# ProPrj_Business-Card.net
KiCad netlist of a schematic drawn in EasyEDA Pro
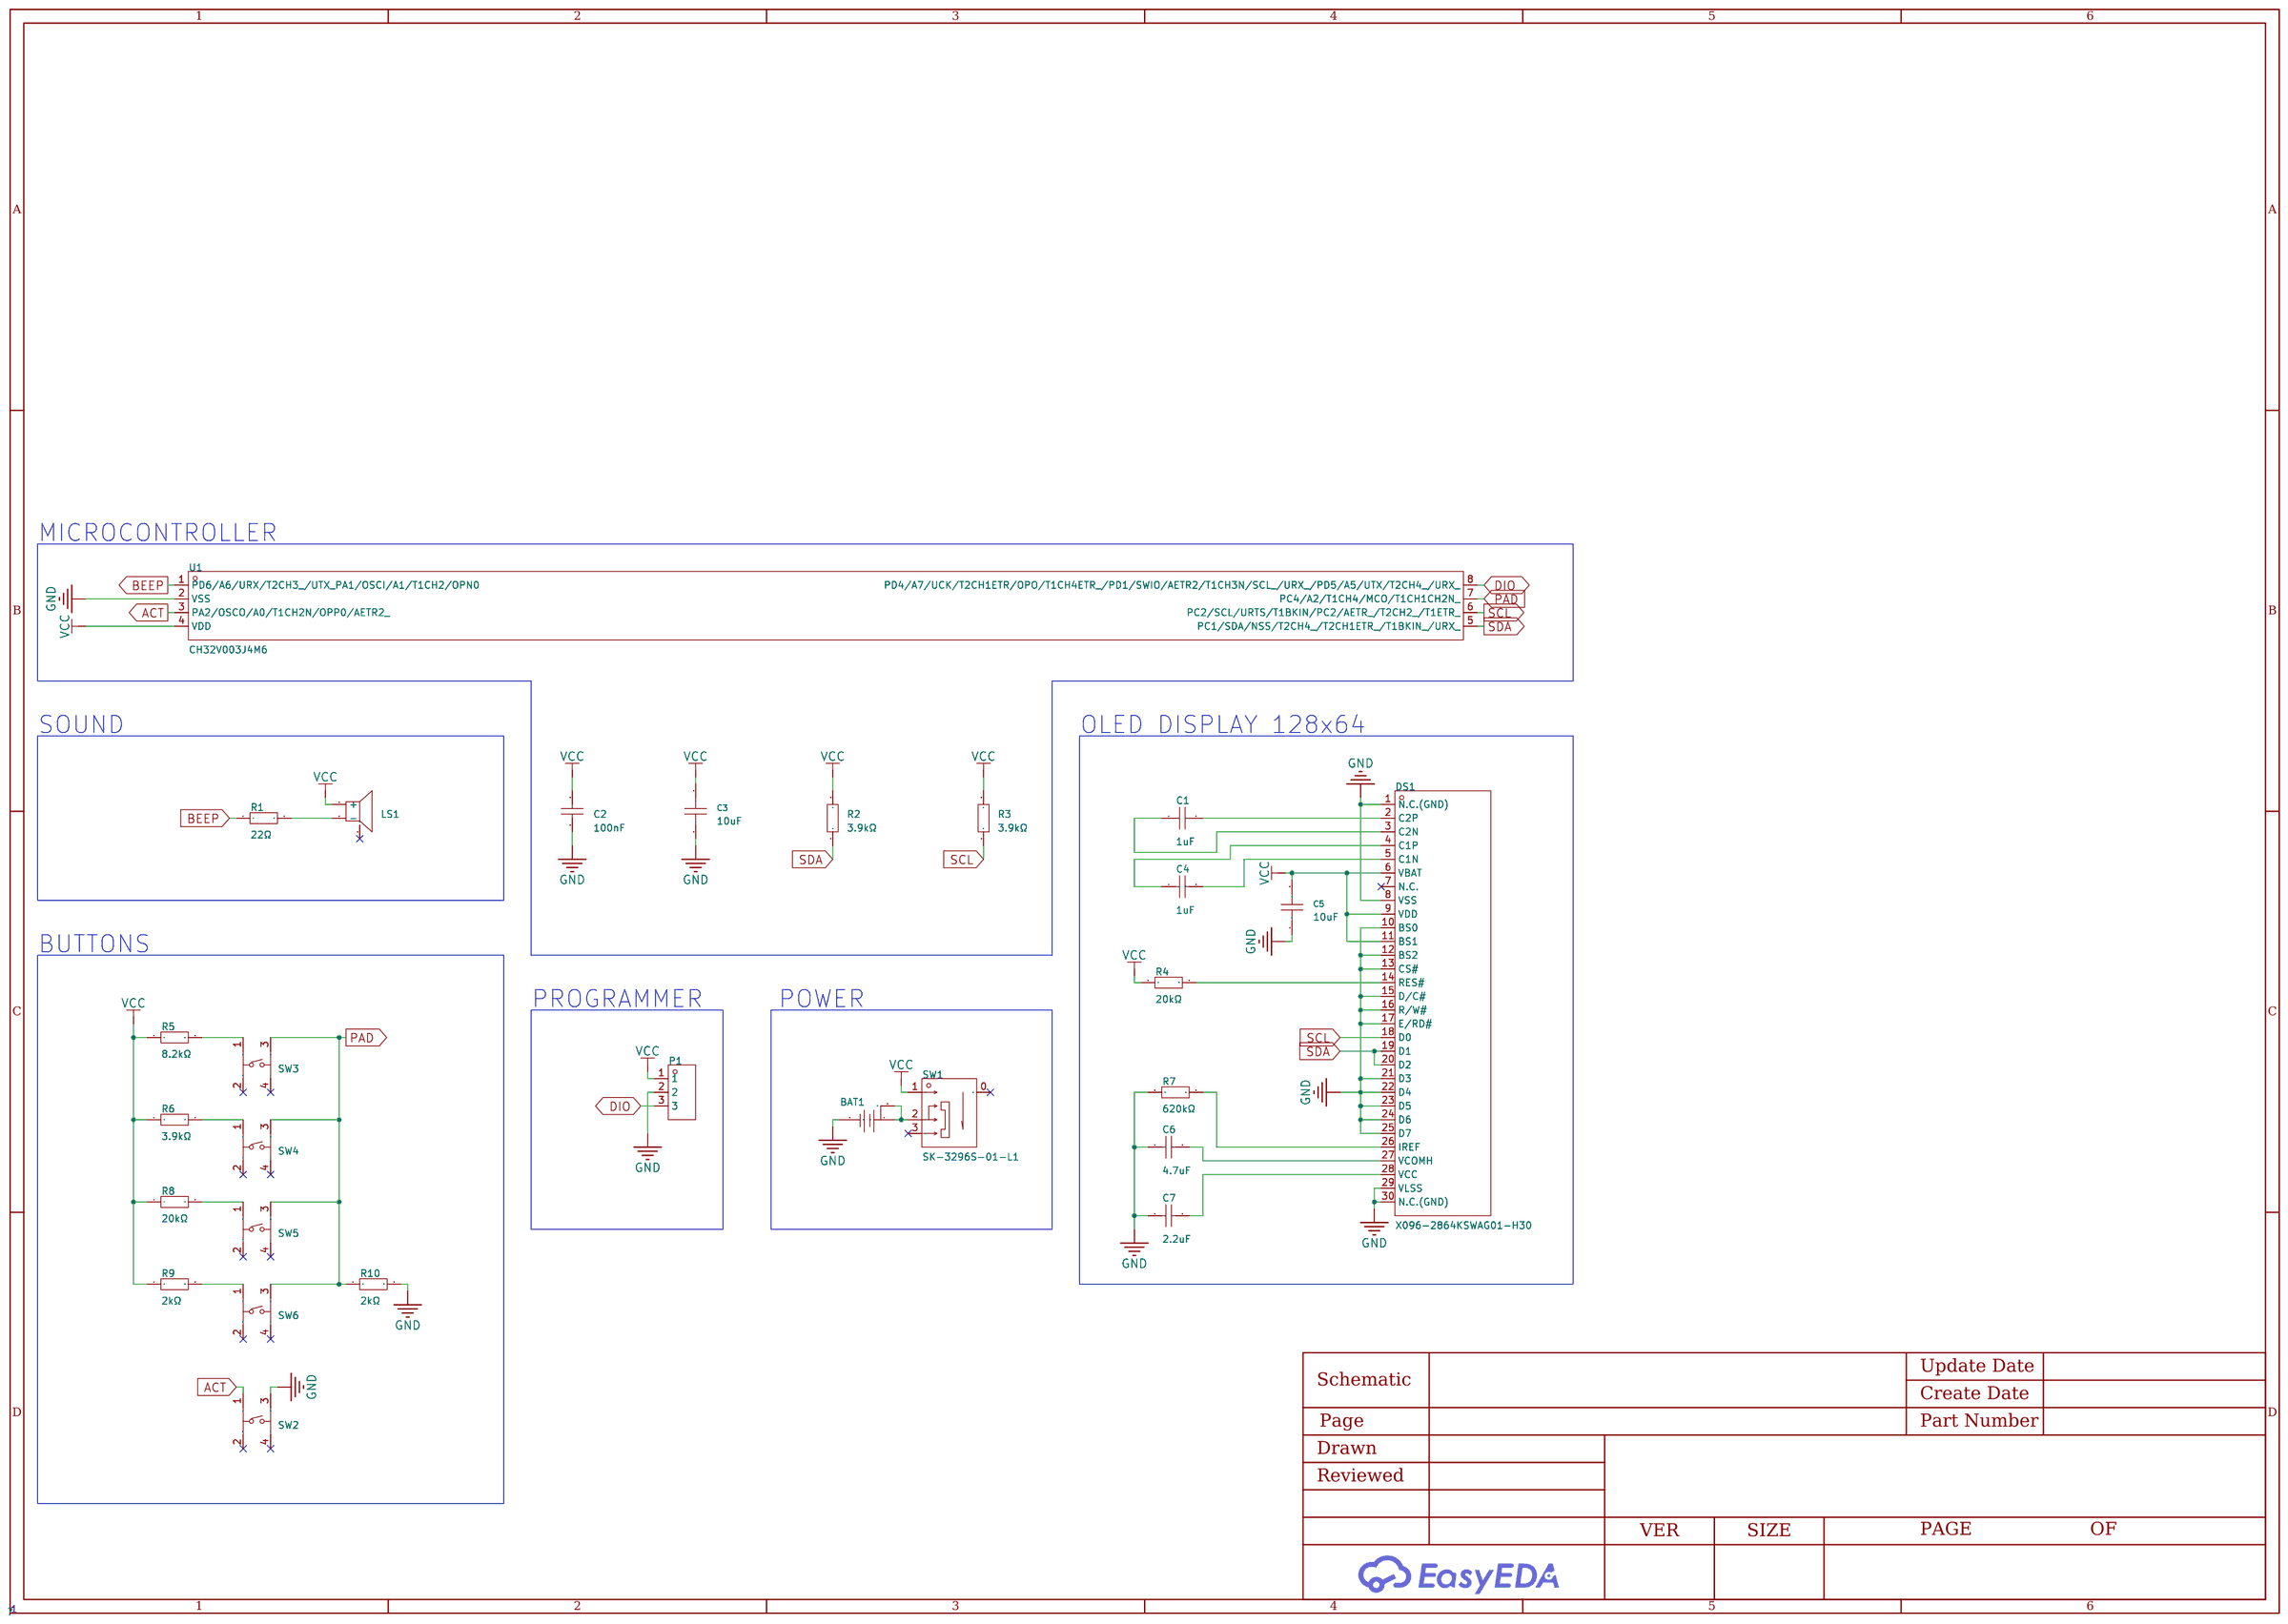
[diagram p0: schematic sheet]

(export (version "E")
  (design (tool "Eeschema 10.0.6"))
  (components
    (comp (ref "BAT1")
      (value "3034TR")
      (footprint "easyedapro:BAT-SMD_3034TR")
      (fields (field (name "Manufacturer") "Keystone"))
      (libsource (lib "easyedapro") (part "3034TR"))
    )
    (comp (ref "C1")
      (value "1uF")
      (footprint "easyedapro:C0805")
      (fields
        (field (name "Manufacturer Part") "GRM21BR71E105KA99L")
        (field (name "Manufacturer") "muRata(村田)")
      )
      (libsource (lib "easyedapro") (part "GRM21BR71E105KA99L"))
    )
    (comp (ref "C2")
      (value "100nF")
      (footprint "easyedapro:C0805")
      (fields
        (field (name "Manufacturer Part") "CC0805KRX7R9BB104")
        (field (name "Manufacturer") "YAGEO(国巨)")
      )
      (libsource (lib "easyedapro") (part "CC0805KRX7R9BB104"))
    )
    (comp (ref "C3")
      (value "10uF")
      (footprint "easyedapro:C0805")
      (fields
        (field (name "Manufacturer Part") "GRM21BR61C106KE15L")
        (field (name "Manufacturer") "muRata(村田)")
      )
      (libsource (lib "easyedapro") (part "GRM21BR61C106KE15L"))
    )
    (comp (ref "C4")
      (value "1uF")
      (footprint "easyedapro:C0805")
      (fields
        (field (name "Manufacturer Part") "GRM21BR71E105KA99L")
        (field (name "Manufacturer") "muRata(村田)")
      )
      (libsource (lib "easyedapro") (part "GRM21BR71E105KA99L"))
    )
    (comp (ref "C5")
      (value "10uF")
      (footprint "easyedapro:C0805")
      (fields
        (field (name "Manufacturer Part") "GRM21BR61C106KE15L")
        (field (name "Manufacturer") "muRata(村田)")
      )
      (libsource (lib "easyedapro") (part "GRM21BR61C106KE15L"))
    )
    (comp (ref "C6")
      (value "4.7uF")
      (footprint "easyedapro:C0805")
      (fields
        (field (name "Manufacturer Part") "GRM21BR61E475KA12L")
        (field (name "Manufacturer") "muRata(村田)")
      )
      (libsource (lib "easyedapro") (part "GRM21BR61E475KA12L"))
    )
    (comp (ref "C7")
      (value "2.2uF")
      (footprint "easyedapro:C0805")
      (fields
        (field (name "Manufacturer Part") "GRM21BR71E225KE11L")
        (field (name "Manufacturer") "muRata(村田)")
      )
      (libsource (lib "easyedapro") (part "GRM21BR71E225KE11L"))
    )
    (comp (ref "DS1")
      (value "X096-2864KSWAG01-H30")
      (footprint "easyedapro:LCD-SMD_X096-2864KSWAG01-H30")
      (description "Main Control Chip:SSD1315 Size:0.96 Pixel Resolution:128x64")
      (fields (field (name "Manufacturer") "Newvision(新智景)"))
      (libsource (lib "easyedapro") (part "X096-2864KSWAG01-H30"))
    )
    (comp (ref "LS1")
      (value "4kHz")
      (footprint "easyedapro:BUZ-SMD_3P-L5.2-W5.2-P3.50-BR")
      (fields (field (name "Manufacturer Part") "MLT-5030") (field (name "Manufacturer") "华能"))
      (libsource (lib "easyedapro") (part "MLT-5030"))
    )
    (comp (ref "P1")
      (value "X6511FRS-03-C85D30")
      (footprint "easyedapro:HDR-SMD_3P-P2.54-H-F-L11.5")
      (fields (field (name "Manufacturer") "XKB Connectivity(中国星坤)"))
      (libsource (lib "easyedapro") (part "X6511FRS-03-C85D30"))
    )
    (comp (ref "R1")
      (value "22Ω")
      (footprint "easyedapro:R0805")
      (fields (field (name "Manufacturer Part") "RC0805FR-0722RL") (field (name "Manufacturer") "YAGEO(国巨)"))
      (libsource (lib "easyedapro") (part "RC0805FR-0722RL"))
    )
    (comp (ref "R2")
      (value "3.9kΩ")
      (footprint "easyedapro:R0805")
      (fields (field (name "Manufacturer Part") "RC0805FR-073K9L") (field (name "Manufacturer") "YAGEO(国巨)"))
      (libsource (lib "easyedapro") (part "RC0805FR-073K9L"))
    )
    (comp (ref "R3")
      (value "3.9kΩ")
      (footprint "easyedapro:R0805")
      (fields (field (name "Manufacturer Part") "RC0805FR-073K9L") (field (name "Manufacturer") "YAGEO(国巨)"))
      (libsource (lib "easyedapro") (part "RC0805FR-073K9L"))
    )
    (comp (ref "R4")
      (value "20kΩ")
      (footprint "easyedapro:R0805")
      (fields (field (name "Manufacturer Part") "RC0805FR-0720KL") (field (name "Manufacturer") "YAGEO(国巨)"))
      (libsource (lib "easyedapro") (part "RC0805FR-0720KL"))
    )
    (comp (ref "R5")
      (value "8.2kΩ")
      (footprint "easyedapro:R0805")
      (fields (field (name "Manufacturer Part") "RC0805FR-078K2L") (field (name "Manufacturer") "YAGEO(国巨)"))
      (libsource (lib "easyedapro") (part "RC0805FR-078K2L"))
    )
    (comp (ref "R6")
      (value "3.9kΩ")
      (footprint "easyedapro:R0805")
      (fields (field (name "Manufacturer Part") "RC0805FR-073K9L") (field (name "Manufacturer") "YAGEO(国巨)"))
      (libsource (lib "easyedapro") (part "RC0805FR-073K9L"))
    )
    (comp (ref "R7")
      (value "620kΩ")
      (footprint "easyedapro:R0805")
      (fields (field (name "Manufacturer Part") "RC0805FR-07620KL") (field (name "Manufacturer") "YAGEO(国巨)"))
      (libsource (lib "easyedapro") (part "RC0805FR-07620KL"))
    )
    (comp (ref "R8")
      (value "20kΩ")
      (footprint "easyedapro:R0805")
      (fields (field (name "Manufacturer Part") "RC0805FR-0720KL") (field (name "Manufacturer") "YAGEO(国巨)"))
      (libsource (lib "easyedapro") (part "RC0805FR-0720KL"))
    )
    (comp (ref "R9")
      (value "2kΩ")
      (footprint "easyedapro:R0805")
      (fields (field (name "Manufacturer Part") "RC0805FR-072KL") (field (name "Manufacturer") "YAGEO(国巨)"))
      (libsource (lib "easyedapro") (part "RC0805FR-072KL"))
    )
    (comp (ref "R10")
      (value "2kΩ")
      (footprint "easyedapro:R0805")
      (fields (field (name "Manufacturer Part") "RC0805FR-072KL") (field (name "Manufacturer") "YAGEO(国巨)"))
      (libsource (lib "easyedapro") (part "RC0805FR-072KL"))
    )
    (comp (ref "SW1")
      (value "SK-3296S-01-L1")
      (footprint "easyedapro:SW-SMD_3P-P1.50_L2.7-W6.6")
      (fields (field (name "Manufacturer") "XKB Connectivity(中国星坤)"))
      (libsource (lib "easyedapro") (part "SK-3296S-01-L1"))
    )
    (comp (ref "SW2")
      (value "TS110926045")
      (footprint "easyedapro:SW-SMD_4P-L4.5-W4.5-P3.00-LS6.6")
      (fields (field (name "Manufacturer") "HanElectricity(瀚源)"))
      (libsource (lib "easyedapro") (part "TS110926045"))
    )
    (comp (ref "SW3")
      (value "TS110926045")
      (footprint "easyedapro:SW-SMD_4P-L4.5-W4.5-P3.00-LS6.6")
      (fields (field (name "Manufacturer") "HanElectricity(瀚源)"))
      (libsource (lib "easyedapro") (part "TS110926045"))
    )
    (comp (ref "SW4")
      (value "TS110926045")
      (footprint "easyedapro:SW-SMD_4P-L4.5-W4.5-P3.00-LS6.6")
      (fields (field (name "Manufacturer") "HanElectricity(瀚源)"))
      (libsource (lib "easyedapro") (part "TS110926045"))
    )
    (comp (ref "SW5")
      (value "TS110926045")
      (footprint "easyedapro:SW-SMD_4P-L4.5-W4.5-P3.00-LS6.6")
      (fields (field (name "Manufacturer") "HanElectricity(瀚源)"))
      (libsource (lib "easyedapro") (part "TS110926045"))
    )
    (comp (ref "SW6")
      (value "TS110926045")
      (footprint "easyedapro:SW-SMD_4P-L4.5-W4.5-P3.00-LS6.6")
      (fields (field (name "Manufacturer") "HanElectricity(瀚源)"))
      (libsource (lib "easyedapro") (part "TS110926045"))
    )
    (comp (ref "U1")
      (value "CH32V003J4M6")
      (footprint "easyedapro:SOP-8_L4.9-W3.8-P1.27-LS6.0-BL")
      (fields (field (name "Manufacturer") "WCH(南京沁恒)"))
      (libsource (lib "easyedapro") (part "CH32V003J4M6_C5346354"))
    )
  )
  (nets
    (net (code "1") (name "ACT") (class "Default")
      (node (ref "SW2") (pin "1") (pinfunction "1_1") (pintype "unspecified"))
      (node (ref "U1") (pin "3") (pinfunction "PA2/OSCO/A0/T1CH2N/OPP0/AETR2__3") (pintype "unspecified"))
    )
    (net (code "2") (name "BEEP") (class "Default")
      (node (ref "R1") (pin "1") (pinfunction "1_1") (pintype "input"))
      (node (ref "U1") (pin "1") (pinfunction "PD6/A6/URX/T2CH3_/UTX_PA1/OSCI/A1/T1CH2/OPN0_1") (pintype "unspecified"))
    )
    (net (code "3") (name "DIO") (class "Default")
      (node (ref "P1") (pin "3") (pinfunction "3_3") (pintype "unspecified"))
      (node (ref "U1") (pin "8") (pinfunction "PD4/A7/UCK/T2CH1ETR/OPO/T1CH4ETR_/PD1/SWIO/AETR2/T1CH3N/SCL_/URX_/PD5/A5/UTX/T2CH4_/URX__8") (pintype "unspecified"))
    )
    (net (code "4") (name "GND") (class "Default")
      (node (ref "BAT1") (pin "2") (pinfunction "2_2") (pintype "input"))
      (node (ref "C2") (pin "1") (pinfunction "1_1") (pintype "input"))
      (node (ref "C3") (pin "1") (pinfunction "1_1") (pintype "input"))
      (node (ref "C5") (pin "1") (pinfunction "1_1") (pintype "input"))
      (node (ref "C6") (pin "1") (pinfunction "1_1") (pintype "input"))
      (node (ref "C7") (pin "1") (pinfunction "1_1") (pintype "input"))
      (node (ref "DS1") (pin "1") (pinfunction "N.C.(GND)_1") (pintype "unspecified"))
      (node (ref "DS1") (pin "10") (pinfunction "BS0_10") (pintype "unspecified"))
      (node (ref "DS1") (pin "12") (pinfunction "BS2_12") (pintype "unspecified"))
      (node (ref "DS1") (pin "13") (pinfunction "CS#_13") (pintype "unspecified"))
      (node (ref "DS1") (pin "15") (pinfunction "D/C#_15") (pintype "unspecified"))
      (node (ref "DS1") (pin "16") (pinfunction "R/W#_16") (pintype "unspecified"))
      (node (ref "DS1") (pin "17") (pinfunction "E/RD#_17") (pintype "unspecified"))
      (node (ref "DS1") (pin "21") (pinfunction "D3_21") (pintype "unspecified"))
      (node (ref "DS1") (pin "22") (pinfunction "D4_22") (pintype "unspecified"))
      (node (ref "DS1") (pin "23") (pinfunction "D5_23") (pintype "unspecified"))
      (node (ref "DS1") (pin "24") (pinfunction "D6_24") (pintype "unspecified"))
      (node (ref "DS1") (pin "25") (pinfunction "D7_25") (pintype "unspecified"))
      (node (ref "DS1") (pin "29") (pinfunction "VLSS_29") (pintype "unspecified"))
      (node (ref "DS1") (pin "30") (pinfunction "N.C.(GND)_30") (pintype "unspecified"))
      (node (ref "DS1") (pin "8") (pinfunction "VSS_8") (pintype "unspecified"))
      (node (ref "P1") (pin "2") (pinfunction "2_2") (pintype "unspecified"))
      (node (ref "R10") (pin "2") (pinfunction "2_2") (pintype "input"))
      (node (ref "R7") (pin "1") (pinfunction "1_1") (pintype "unspecified"))
      (node (ref "SW2") (pin "3") (pinfunction "3_3") (pintype "unspecified"))
      (node (ref "U1") (pin "2") (pinfunction "VSS_2") (pintype "unspecified"))
    )
    (net (code "5") (name "Net-(BAT1-Pad1)") (class "Default")
      (node (ref "BAT1") (pin "1") (pinfunction "1_1") (pintype "input"))
      (node (ref "BAT1") (pin "3") (pinfunction "3_3") (pintype "input"))
      (node (ref "SW1") (pin "2") (pinfunction "2_2") (pintype "unspecified"))
    )
    (net (code "6") (name "Net-(DS1-C1N)") (class "Default")
      (node (ref "C4") (pin "2") (pinfunction "2_2") (pintype "input"))
      (node (ref "DS1") (pin "5") (pinfunction "C1N_5") (pintype "unspecified"))
    )
    (net (code "7") (name "Net-(DS1-C1P)") (class "Default")
      (node (ref "C4") (pin "1") (pinfunction "1_1") (pintype "input"))
      (node (ref "DS1") (pin "4") (pinfunction "C1P_4") (pintype "unspecified"))
    )
    (net (code "8") (name "Net-(DS1-C2N)") (class "Default")
      (node (ref "C1") (pin "1") (pinfunction "1_1") (pintype "input"))
      (node (ref "DS1") (pin "3") (pinfunction "C2N_3") (pintype "unspecified"))
    )
    (net (code "9") (name "Net-(DS1-C2P)") (class "Default")
      (node (ref "C1") (pin "2") (pinfunction "2_2") (pintype "input"))
      (node (ref "DS1") (pin "2") (pinfunction "C2P_2") (pintype "unspecified"))
    )
    (net (code "10") (name "Net-(DS1-IREF)") (class "Default")
      (node (ref "DS1") (pin "26") (pinfunction "IREF_26") (pintype "unspecified"))
      (node (ref "R7") (pin "2") (pinfunction "2_2") (pintype "unspecified"))
    )
    (net (code "11") (name "Net-(DS1-RES#)") (class "Default")
      (node (ref "DS1") (pin "14") (pinfunction "RES#_14") (pintype "unspecified"))
      (node (ref "R4") (pin "2") (pinfunction "2_2") (pintype "input"))
    )
    (net (code "12") (name "Net-(DS1-VCC)") (class "Default")
      (node (ref "C7") (pin "2") (pinfunction "2_2") (pintype "input"))
      (node (ref "DS1") (pin "28") (pinfunction "VCC_28") (pintype "unspecified"))
    )
    (net (code "13") (name "Net-(DS1-VCOMH)") (class "Default")
      (node (ref "C6") (pin "2") (pinfunction "2_2") (pintype "input"))
      (node (ref "DS1") (pin "27") (pinfunction "VCOMH_27") (pintype "unspecified"))
    )
    (net (code "14") (name "Net-(LS1--)") (class "Default")
      (node (ref "LS1") (pin "3") (pinfunction "-_3") (pintype "input"))
      (node (ref "R1") (pin "2") (pinfunction "2_2") (pintype "input"))
    )
    (net (code "15") (name "Net-(R5-Pad2)") (class "Default")
      (node (ref "R5") (pin "2") (pinfunction "2_2") (pintype "input"))
      (node (ref "SW3") (pin "1") (pinfunction "1_1") (pintype "unspecified"))
    )
    (net (code "16") (name "Net-(R6-Pad2)") (class "Default")
      (node (ref "R6") (pin "2") (pinfunction "2_2") (pintype "unspecified"))
      (node (ref "SW4") (pin "1") (pinfunction "1_1") (pintype "unspecified"))
    )
    (net (code "17") (name "Net-(R8-Pad2)") (class "Default")
      (node (ref "R8") (pin "2") (pinfunction "2_2") (pintype "input"))
      (node (ref "SW5") (pin "1") (pinfunction "1_1") (pintype "unspecified"))
    )
    (net (code "18") (name "Net-(R9-Pad2)") (class "Default")
      (node (ref "R9") (pin "2") (pinfunction "2_2") (pintype "input"))
      (node (ref "SW6") (pin "1") (pinfunction "1_1") (pintype "unspecified"))
    )
    (net (code "19") (name "PAD") (class "Default")
      (node (ref "R10") (pin "1") (pinfunction "1_1") (pintype "input"))
      (node (ref "SW3") (pin "3") (pinfunction "3_3") (pintype "unspecified"))
      (node (ref "SW4") (pin "3") (pinfunction "3_3") (pintype "unspecified"))
      (node (ref "SW5") (pin "3") (pinfunction "3_3") (pintype "unspecified"))
      (node (ref "SW6") (pin "3") (pinfunction "3_3") (pintype "unspecified"))
      (node (ref "U1") (pin "7") (pinfunction "PC4/A2/T1CH4/MCO/T1CH1CH2N__7") (pintype "unspecified"))
    )
    (net (code "20") (name "SCL") (class "Default")
      (node (ref "DS1") (pin "18") (pinfunction "D0_18") (pintype "unspecified"))
      (node (ref "R3") (pin "1") (pinfunction "1_1") (pintype "unspecified"))
      (node (ref "U1") (pin "6") (pinfunction "PC2/SCL/URTS/T1BKIN/PC2/AETR_/T2CH2_/T1ETR__6") (pintype "unspecified"))
    )
    (net (code "21") (name "SDA") (class "Default")
      (node (ref "DS1") (pin "19") (pinfunction "D1_19") (pintype "unspecified"))
      (node (ref "DS1") (pin "20") (pinfunction "D2_20") (pintype "unspecified"))
      (node (ref "R2") (pin "1") (pinfunction "1_1") (pintype "unspecified"))
      (node (ref "U1") (pin "5") (pinfunction "PC1/SDA/NSS/T2CH4_/T2CH1ETR_/T1BKIN_/URX__5") (pintype "unspecified"))
    )
    (net (code "22") (name "VCC") (class "Default")
      (node (ref "C2") (pin "2") (pinfunction "2_2") (pintype "input"))
      (node (ref "C3") (pin "2") (pinfunction "2_2") (pintype "input"))
      (node (ref "C5") (pin "2") (pinfunction "2_2") (pintype "input"))
      (node (ref "DS1") (pin "11") (pinfunction "BS1_11") (pintype "unspecified"))
      (node (ref "DS1") (pin "6") (pinfunction "VBAT_6") (pintype "unspecified"))
      (node (ref "DS1") (pin "9") (pinfunction "VDD_9") (pintype "unspecified"))
      (node (ref "LS1") (pin "2") (pinfunction "+_2") (pintype "input"))
      (node (ref "P1") (pin "1") (pinfunction "1_1") (pintype "unspecified"))
      (node (ref "R2") (pin "2") (pinfunction "2_2") (pintype "unspecified"))
      (node (ref "R3") (pin "2") (pinfunction "2_2") (pintype "unspecified"))
      (node (ref "R4") (pin "1") (pinfunction "1_1") (pintype "input"))
      (node (ref "R5") (pin "1") (pinfunction "1_1") (pintype "input"))
      (node (ref "R6") (pin "1") (pinfunction "1_1") (pintype "unspecified"))
      (node (ref "R8") (pin "1") (pinfunction "1_1") (pintype "input"))
      (node (ref "R9") (pin "1") (pinfunction "1_1") (pintype "input"))
      (node (ref "SW1") (pin "1") (pinfunction "1_1") (pintype "unspecified"))
      (node (ref "U1") (pin "4") (pinfunction "VDD_4") (pintype "unspecified"))
    )
    (net (code "23") (name "unconnected-(DS1-N.C.-Pad7)") (class "Default")
      (node (ref "DS1") (pin "7") (pinfunction "N.C._7") (pintype "unspecified+no_connect"))
    )
    (net (code "24") (name "unconnected-(LS1-NC-Pad1)") (class "Default")
      (node (ref "LS1") (pin "1") (pinfunction "NC_1") (pintype "input+no_connect"))
    )
    (net (code "25") (name "unconnected-(SW1-Pad0)") (class "Default")
      (node (ref "SW1") (pin "0") (pinfunction "0_0") (pintype "unspecified+no_connect"))
    )
    (net (code "26") (name "unconnected-(SW1-Pad3)") (class "Default")
      (node (ref "SW1") (pin "3") (pinfunction "3_3") (pintype "unspecified+no_connect"))
    )
    (net (code "27") (name "unconnected-(SW2-Pad2)") (class "Default")
      (node (ref "SW2") (pin "2") (pinfunction "2_2") (pintype "unspecified+no_connect"))
    )
    (net (code "28") (name "unconnected-(SW2-Pad4)") (class "Default")
      (node (ref "SW2") (pin "4") (pinfunction "4_4") (pintype "unspecified+no_connect"))
    )
    (net (code "29") (name "unconnected-(SW3-Pad2)") (class "Default")
      (node (ref "SW3") (pin "2") (pinfunction "2_2") (pintype "unspecified+no_connect"))
    )
    (net (code "30") (name "unconnected-(SW3-Pad4)") (class "Default")
      (node (ref "SW3") (pin "4") (pinfunction "4_4") (pintype "unspecified+no_connect"))
    )
    (net (code "31") (name "unconnected-(SW4-Pad2)") (class "Default")
      (node (ref "SW4") (pin "2") (pinfunction "2_2") (pintype "unspecified+no_connect"))
    )
    (net (code "32") (name "unconnected-(SW4-Pad4)") (class "Default")
      (node (ref "SW4") (pin "4") (pinfunction "4_4") (pintype "unspecified+no_connect"))
    )
    (net (code "33") (name "unconnected-(SW5-Pad2)") (class "Default")
      (node (ref "SW5") (pin "2") (pinfunction "2_2") (pintype "unspecified+no_connect"))
    )
    (net (code "34") (name "unconnected-(SW5-Pad4)") (class "Default")
      (node (ref "SW5") (pin "4") (pinfunction "4_4") (pintype "unspecified+no_connect"))
    )
    (net (code "35") (name "unconnected-(SW6-Pad2)") (class "Default")
      (node (ref "SW6") (pin "2") (pinfunction "2_2") (pintype "unspecified+no_connect"))
    )
    (net (code "36") (name "unconnected-(SW6-Pad4)") (class "Default")
      (node (ref "SW6") (pin "4") (pinfunction "4_4") (pintype "unspecified+no_connect"))
    )
  )
)
